# lp_propeller.net
KiCad netlist of a schematic drawn in EAGLE
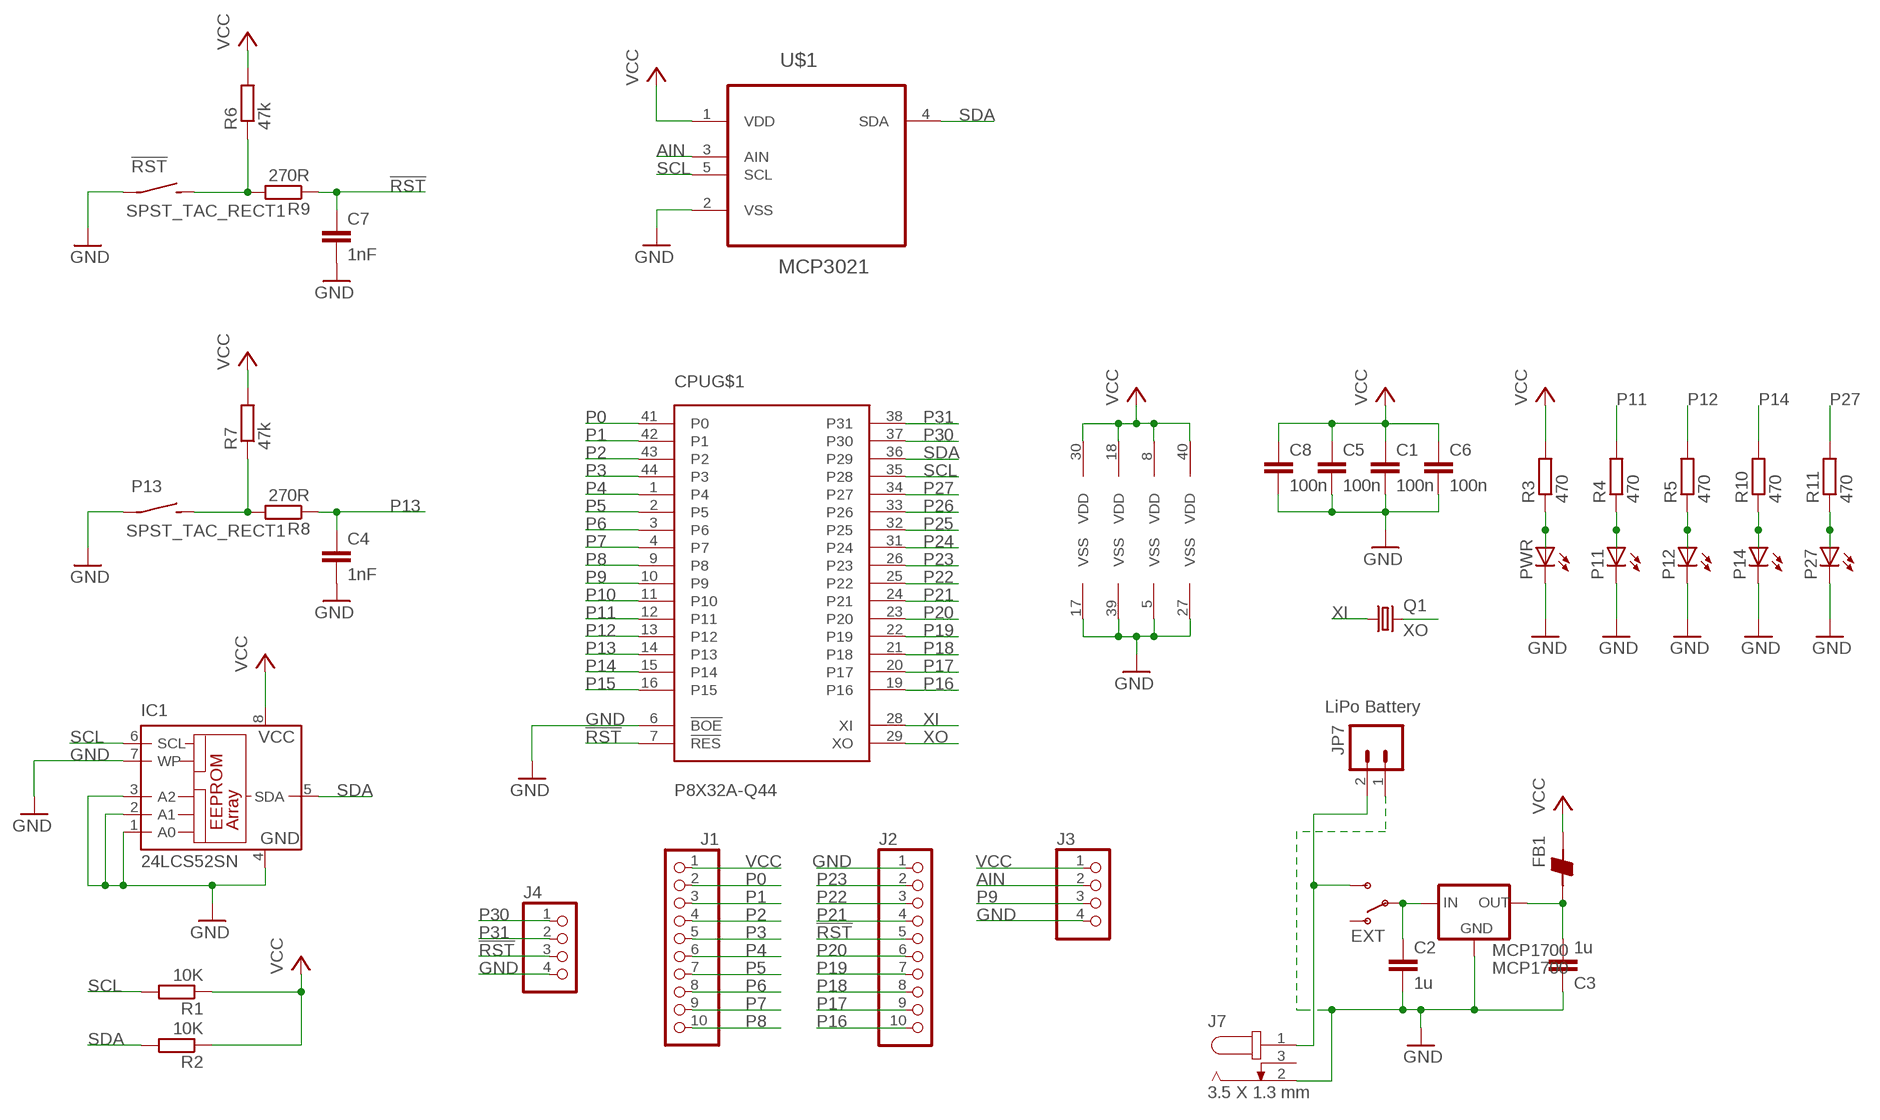
[diagram p0: schematic, sheet 1]

(export (version "E")
  (design (tool "Eeschema 10.0.6"))
  (components
    (comp (ref "!RST")
      (value "SPST_TAC_RECT1")
      (footprint "eagle-import:6MMTACTILE_RECT")
      (libsource (lib "eagle-import") (part "SPST_TAC_RECT1"))
    )
    (comp (ref "C1")
      (value "100n")
      (footprint "eagle-import:C0805")
      (libsource (lib "eagle-import") (part "C-EUC0805"))
    )
    (comp (ref "C2")
      (value "1u")
      (footprint "eagle-import:C0805")
      (libsource (lib "eagle-import") (part "C-EUC0805"))
    )
    (comp (ref "C3")
      (value "1u")
      (footprint "eagle-import:C0805")
      (libsource (lib "eagle-import") (part "C-EUC0805"))
    )
    (comp (ref "C4")
      (value "1nF")
      (footprint "eagle-import:C0805")
      (libsource (lib "eagle-import") (part "resistor_C-EUC0805"))
    )
    (comp (ref "C5")
      (value "100n")
      (footprint "eagle-import:C0805")
      (libsource (lib "eagle-import") (part "C-EUC0805"))
    )
    (comp (ref "C6")
      (value "100n")
      (footprint "eagle-import:C0805")
      (libsource (lib "eagle-import") (part "C-EUC0805"))
    )
    (comp (ref "C7")
      (value "1nF")
      (footprint "eagle-import:C0805")
      (libsource (lib "eagle-import") (part "resistor_C-EUC0805"))
    )
    (comp (ref "C8")
      (value "100n")
      (footprint "eagle-import:C0805")
      (libsource (lib "eagle-import") (part "C-EUC0805"))
    )
    (comp (ref "CPU")
      (value "P8X32A-Q44")
      (footprint "eagle-import:LQFP-44")
      (libsource (lib "eagle-import") (part "P8X32A-Q44"))
    )
    (comp (ref "FB1")
      (value "BEAD-0805")
      (footprint "eagle-import:0805")
      (libsource (lib "eagle-import") (part "BEAD-0805"))
    )
    (comp (ref "IC1")
      (value "24LCS52SN")
      (footprint "eagle-import:SO-08")
      (fields (field (name "MF") "MICROCHIP") (field (name "MPN") "24LCS52-I/SN"))
      (libsource (lib "eagle-import") (part "24SNLCS52"))
    )
    (comp (ref "J1")
      (value "PH1X10OCT076")
      (footprint "eagle-import:PH1X10OCT76")
      (libsource (lib "eagle-import") (part "PH1X10OCT076"))
    )
    (comp (ref "J2")
      (value "PH1X10OCT076")
      (footprint "eagle-import:PH1X10OCT76")
      (libsource (lib "eagle-import") (part "PH1X10OCT076"))
    )
    (comp (ref "J3")
      (value "PINHD-1X4")
      (footprint "eagle-import:1X04")
      (libsource (lib "eagle-import") (part "PINHD-1X4"))
    )
    (comp (ref "J4")
      (value "PINHD-1X4")
      (footprint "eagle-import:1X04")
      (libsource (lib "eagle-import") (part "PINHD-1X4"))
    )
    (comp (ref "J7")
      (value "3.5 X 1.3 mm")
      (footprint "eagle-import:3.5X1.3MM_DC_JACK")
      (libsource (lib "eagle-import") (part "DC_JACK_3.5X1.3MM"))
    )
    (comp (ref "JP7")
      (value "LiPo Battery")
      (footprint "eagle-import:JST-2-PTH")
      (libsource (lib "eagle-import") (part "M02JST-PTH-2"))
    )
    (comp (ref "MCP1700")
      (value "MCP1700")
      (footprint "eagle-import:SOT-23")
      (libsource (lib "eagle-import") (part "MCP1700SOT-23"))
    )
    (comp (ref "ON")
      (value "EXT")
      (footprint "eagle-import:SWITCH-SPDT")
      (libsource (lib "eagle-import") (part "SWITCH-SPSTPTH"))
    )
    (comp (ref "P11")
      (value "LEDCHIPLED_1206")
      (footprint "eagle-import:CHIPLED_1206")
      (libsource (lib "eagle-import") (part "LEDCHIPLED_1206"))
    )
    (comp (ref "P12")
      (value "LEDCHIPLED_1206")
      (footprint "eagle-import:CHIPLED_1206")
      (libsource (lib "eagle-import") (part "LEDCHIPLED_1206"))
    )
    (comp (ref "P13")
      (value "SPST_TAC_RECT1")
      (footprint "eagle-import:6MMTACTILE_RECT")
      (libsource (lib "eagle-import") (part "SPST_TAC_RECT1"))
    )
    (comp (ref "P14")
      (value "LEDCHIPLED_1206")
      (footprint "eagle-import:CHIPLED_1206")
      (libsource (lib "eagle-import") (part "LEDCHIPLED_1206"))
    )
    (comp (ref "P27")
      (value "LEDCHIPLED_1206")
      (footprint "eagle-import:CHIPLED_1206")
      (libsource (lib "eagle-import") (part "LEDCHIPLED_1206"))
    )
    (comp (ref "PWR")
      (value "LEDCHIPLED_1206")
      (footprint "eagle-import:CHIPLED_1206")
      (libsource (lib "eagle-import") (part "LEDCHIPLED_1206"))
    )
    (comp (ref "Q1")
      (value "CRYSTALHC49S")
      (footprint "eagle-import:HC49_S")
      (libsource (lib "eagle-import") (part "CRYSTALHC49S"))
    )
    (comp (ref "R1")
      (value "10K")
      (footprint "eagle-import:R0805")
      (libsource (lib "eagle-import") (part "R-EU_R0805"))
    )
    (comp (ref "R2")
      (value "10K")
      (footprint "eagle-import:R0805")
      (libsource (lib "eagle-import") (part "R-EU_R0805"))
    )
    (comp (ref "R3")
      (value "470")
      (footprint "eagle-import:R0805")
      (libsource (lib "eagle-import") (part "R-EU_R0805"))
    )
    (comp (ref "R4")
      (value "470")
      (footprint "eagle-import:R0805")
      (libsource (lib "eagle-import") (part "R-EU_R0805"))
    )
    (comp (ref "R5")
      (value "470")
      (footprint "eagle-import:R0805")
      (libsource (lib "eagle-import") (part "R-EU_R0805"))
    )
    (comp (ref "R6")
      (value "47k")
      (footprint "eagle-import:R0805")
      (libsource (lib "eagle-import") (part "R-EU_R0805"))
    )
    (comp (ref "R7")
      (value "47k")
      (footprint "eagle-import:R0805")
      (libsource (lib "eagle-import") (part "R-EU_R0805"))
    )
    (comp (ref "R8")
      (value "270R")
      (footprint "eagle-import:R0805")
      (libsource (lib "eagle-import") (part "R-EU_R0805"))
    )
    (comp (ref "R9")
      (value "270R")
      (footprint "eagle-import:R0805")
      (libsource (lib "eagle-import") (part "R-EU_R0805"))
    )
    (comp (ref "R10")
      (value "470")
      (footprint "eagle-import:R0805")
      (libsource (lib "eagle-import") (part "R-EU_R0805"))
    )
    (comp (ref "R11")
      (value "470")
      (footprint "eagle-import:R0805")
      (libsource (lib "eagle-import") (part "R-EU_R0805"))
    )
    (comp (ref "U$1")
      (value "MCP3021")
      (footprint "eagle-import:SOT95P270X145-5N")
      (fields (field (name "MPN") "MCP3021A5T-E/OT"))
      (libsource (lib "eagle-import") (part "MCP3021A5T-E/OT"))
    )
  )
  (nets
    (net (code "1") (name "/AIN") (class "Default")
      (node (ref "J3") (pin "2") (pinfunction "2_2") (pintype "passive"))
      (node (ref "U$1") (pin "3") (pinfunction "AIN_3") (pintype "input"))
    )
    (net (code "2") (name "/P0") (class "Default")
      (node (ref "CPU") (pin "41") (pinfunction "P0_41") (pintype "bidirectional"))
      (node (ref "J1") (pin "2") (pinfunction "2_2") (pintype "passive"))
    )
    (net (code "3") (name "/P1") (class "Default")
      (node (ref "CPU") (pin "42") (pinfunction "P1_42") (pintype "bidirectional"))
      (node (ref "J1") (pin "3") (pinfunction "3_3") (pintype "passive"))
    )
    (net (code "4") (name "/P2") (class "Default")
      (node (ref "CPU") (pin "43") (pinfunction "P2_43") (pintype "bidirectional"))
      (node (ref "J1") (pin "4") (pinfunction "4_4") (pintype "passive"))
    )
    (net (code "5") (name "/P3") (class "Default")
      (node (ref "CPU") (pin "44") (pinfunction "P3_44") (pintype "bidirectional"))
      (node (ref "J1") (pin "5") (pinfunction "5_5") (pintype "passive"))
    )
    (net (code "6") (name "/P4") (class "Default")
      (node (ref "CPU") (pin "1") (pinfunction "P4_1") (pintype "bidirectional"))
      (node (ref "J1") (pin "6") (pinfunction "6_6") (pintype "passive"))
    )
    (net (code "7") (name "/P5") (class "Default")
      (node (ref "CPU") (pin "2") (pinfunction "P5_2") (pintype "bidirectional"))
      (node (ref "J1") (pin "7") (pinfunction "7_7") (pintype "passive"))
    )
    (net (code "8") (name "/P6") (class "Default")
      (node (ref "CPU") (pin "3") (pinfunction "P6_3") (pintype "bidirectional"))
      (node (ref "J1") (pin "8") (pinfunction "8_8") (pintype "passive"))
    )
    (net (code "9") (name "/P7") (class "Default")
      (node (ref "CPU") (pin "4") (pinfunction "P7_4") (pintype "bidirectional"))
      (node (ref "J1") (pin "9") (pinfunction "9_9") (pintype "passive"))
    )
    (net (code "10") (name "/P8") (class "Default")
      (node (ref "CPU") (pin "9") (pinfunction "P8_9") (pintype "bidirectional"))
      (node (ref "J1") (pin "10") (pinfunction "10_10") (pintype "passive"))
    )
    (net (code "11") (name "/P9") (class "Default")
      (node (ref "CPU") (pin "10") (pinfunction "P9_10") (pintype "bidirectional"))
      (node (ref "J3") (pin "3") (pinfunction "3_3") (pintype "passive"))
    )
    (net (code "12") (name "/P10") (class "Default")
      (node (ref "CPU") (pin "11") (pinfunction "P10_11") (pintype "bidirectional"))
    )
    (net (code "13") (name "/P11") (class "Default")
      (node (ref "CPU") (pin "12") (pinfunction "P11_12") (pintype "bidirectional"))
      (node (ref "R4") (pin "2") (pinfunction "2_2") (pintype "passive"))
    )
    (net (code "14") (name "/P12") (class "Default")
      (node (ref "CPU") (pin "13") (pinfunction "P12_13") (pintype "bidirectional"))
      (node (ref "R5") (pin "2") (pinfunction "2_2") (pintype "passive"))
    )
    (net (code "15") (name "/P13") (class "Default")
      (node (ref "C4") (pin "1") (pinfunction "1_1") (pintype "passive"))
      (node (ref "CPU") (pin "14") (pinfunction "P13_14") (pintype "bidirectional"))
      (node (ref "R8") (pin "1") (pinfunction "1_1") (pintype "passive"))
    )
    (net (code "16") (name "/P14") (class "Default")
      (node (ref "CPU") (pin "15") (pinfunction "P14_15") (pintype "bidirectional"))
      (node (ref "R10") (pin "2") (pinfunction "2_2") (pintype "passive"))
    )
    (net (code "17") (name "/P15") (class "Default")
      (node (ref "CPU") (pin "16") (pinfunction "P15_16") (pintype "bidirectional"))
    )
    (net (code "18") (name "/P16") (class "Default")
      (node (ref "CPU") (pin "19") (pinfunction "P16_19") (pintype "bidirectional"))
      (node (ref "J2") (pin "10") (pinfunction "10_10") (pintype "passive"))
    )
    (net (code "19") (name "/P17") (class "Default")
      (node (ref "CPU") (pin "20") (pinfunction "P17_20") (pintype "bidirectional"))
      (node (ref "J2") (pin "9") (pinfunction "9_9") (pintype "passive"))
    )
    (net (code "20") (name "/P18") (class "Default")
      (node (ref "CPU") (pin "21") (pinfunction "P18_21") (pintype "bidirectional"))
      (node (ref "J2") (pin "8") (pinfunction "8_8") (pintype "passive"))
    )
    (net (code "21") (name "/P19") (class "Default")
      (node (ref "CPU") (pin "22") (pinfunction "P19_22") (pintype "bidirectional"))
      (node (ref "J2") (pin "7") (pinfunction "7_7") (pintype "passive"))
    )
    (net (code "22") (name "/P20") (class "Default")
      (node (ref "CPU") (pin "23") (pinfunction "P20_23") (pintype "bidirectional"))
      (node (ref "J2") (pin "6") (pinfunction "6_6") (pintype "passive"))
    )
    (net (code "23") (name "/P21") (class "Default")
      (node (ref "CPU") (pin "24") (pinfunction "P21_24") (pintype "bidirectional"))
      (node (ref "J2") (pin "4") (pinfunction "4_4") (pintype "passive"))
    )
    (net (code "24") (name "/P22") (class "Default")
      (node (ref "CPU") (pin "25") (pinfunction "P22_25") (pintype "bidirectional"))
      (node (ref "J2") (pin "3") (pinfunction "3_3") (pintype "passive"))
    )
    (net (code "25") (name "/P23") (class "Default")
      (node (ref "CPU") (pin "26") (pinfunction "P23_26") (pintype "bidirectional"))
      (node (ref "J2") (pin "2") (pinfunction "2_2") (pintype "passive"))
    )
    (net (code "26") (name "/P24") (class "Default")
      (node (ref "CPU") (pin "31") (pinfunction "P24_31") (pintype "bidirectional"))
    )
    (net (code "27") (name "/P25") (class "Default")
      (node (ref "CPU") (pin "32") (pinfunction "P25_32") (pintype "bidirectional"))
    )
    (net (code "28") (name "/P26") (class "Default")
      (node (ref "CPU") (pin "33") (pinfunction "P26_33") (pintype "bidirectional"))
    )
    (net (code "29") (name "/P27") (class "Default")
      (node (ref "CPU") (pin "34") (pinfunction "P27_34") (pintype "bidirectional"))
      (node (ref "R11") (pin "2") (pinfunction "2_2") (pintype "passive"))
    )
    (net (code "30") (name "/P30") (class "Default")
      (node (ref "CPU") (pin "37") (pinfunction "P30_37") (pintype "bidirectional"))
      (node (ref "J4") (pin "1") (pinfunction "1_1") (pintype "passive"))
    )
    (net (code "31") (name "/P31") (class "Default")
      (node (ref "CPU") (pin "38") (pinfunction "P31_38") (pintype "bidirectional"))
      (node (ref "J4") (pin "2") (pinfunction "2_2") (pintype "passive"))
    )
    (net (code "32") (name "/SCL") (class "Default")
      (node (ref "CPU") (pin "35") (pinfunction "P28_35") (pintype "bidirectional"))
      (node (ref "IC1") (pin "6") (pinfunction "SCL_6") (pintype "input"))
      (node (ref "R1") (pin "2") (pinfunction "2_2") (pintype "passive"))
      (node (ref "U$1") (pin "5") (pinfunction "SCL_5") (pintype "input"))
    )
    (net (code "33") (name "/SDA") (class "Default")
      (node (ref "CPU") (pin "36") (pinfunction "P29_36") (pintype "bidirectional"))
      (node (ref "IC1") (pin "5") (pinfunction "SDA_5") (pintype "bidirectional"))
      (node (ref "R2") (pin "2") (pinfunction "2_2") (pintype "passive"))
      (node (ref "U$1") (pin "4") (pinfunction "SDA_4") (pintype "bidirectional"))
    )
    (net (code "34") (name "/XI") (class "Default")
      (node (ref "CPU") (pin "28") (pinfunction "XI_28") (pintype "input"))
      (node (ref "Q1") (pin "1") (pinfunction "1_1") (pintype "passive"))
    )
    (net (code "35") (name "/XO") (class "Default")
      (node (ref "CPU") (pin "29") (pinfunction "XO_29") (pintype "output"))
      (node (ref "Q1") (pin "2") (pinfunction "2_2") (pintype "passive"))
    )
    (net (code "36") (name "/~{RST}") (class "Default")
      (node (ref "C7") (pin "1") (pinfunction "1_1") (pintype "passive"))
      (node (ref "CPU") (pin "7") (pinfunction "~{RES}_7") (pintype "bidirectional"))
      (node (ref "J2") (pin "5") (pinfunction "5_5") (pintype "passive"))
      (node (ref "J4") (pin "3") (pinfunction "3_3") (pintype "passive"))
      (node (ref "R9") (pin "1") (pinfunction "1_1") (pintype "passive"))
    )
    (net (code "37") (name "GND") (class "Default")
      (node (ref "!RST") (pin "P$1") (pinfunction "P_P$1") (pintype "passive"))
      (node (ref "C1") (pin "2") (pinfunction "2_2") (pintype "passive"))
      (node (ref "C2") (pin "2") (pinfunction "2_2") (pintype "passive"))
      (node (ref "C3") (pin "1") (pinfunction "1_1") (pintype "passive"))
      (node (ref "C4") (pin "2") (pinfunction "2_2") (pintype "passive"))
      (node (ref "C5") (pin "2") (pinfunction "2_2") (pintype "passive"))
      (node (ref "C6") (pin "2") (pinfunction "2_2") (pintype "passive"))
      (node (ref "C7") (pin "2") (pinfunction "2_2") (pintype "passive"))
      (node (ref "C8") (pin "2") (pinfunction "2_2") (pintype "passive"))
      (node (ref "CPU") (pin "17") (pinfunction "VSS_17") (pintype "input"))
      (node (ref "CPU") (pin "27") (pinfunction "VSS_27") (pintype "input"))
      (node (ref "CPU") (pin "39") (pinfunction "VSS_39") (pintype "input"))
      (node (ref "CPU") (pin "5") (pinfunction "VSS_5") (pintype "input"))
      (node (ref "CPU") (pin "6") (pinfunction "~{BOE}_6") (pintype "input"))
      (node (ref "IC1") (pin "1") (pinfunction "A0_1") (pintype "input"))
      (node (ref "IC1") (pin "2") (pinfunction "A1_2") (pintype "input"))
      (node (ref "IC1") (pin "3") (pinfunction "A2_3") (pintype "input"))
      (node (ref "IC1") (pin "4") (pinfunction "GND_4") (pintype "power_in"))
      (node (ref "IC1") (pin "7") (pinfunction "WP_7") (pintype "input"))
      (node (ref "J2") (pin "1") (pinfunction "1_1") (pintype "passive"))
      (node (ref "J3") (pin "4") (pinfunction "4_4") (pintype "passive"))
      (node (ref "J4") (pin "4") (pinfunction "4_4") (pintype "passive"))
      (node (ref "J7") (pin "2") (pinfunction "2_2") (pintype "passive"))
      (node (ref "JP7") (pin "1") (pinfunction "1_1") (pintype "passive"))
      (node (ref "MCP1700") (pin "1") (pinfunction "GND_1") (pintype "input"))
      (node (ref "P11") (pin "C") (pinfunction "C_C") (pintype "passive"))
      (node (ref "P12") (pin "C") (pinfunction "C_C") (pintype "passive"))
      (node (ref "P13") (pin "P$1") (pinfunction "P_P$1") (pintype "passive"))
      (node (ref "P14") (pin "C") (pinfunction "C_C") (pintype "passive"))
      (node (ref "P27") (pin "C") (pinfunction "C_C") (pintype "passive"))
      (node (ref "PWR") (pin "C") (pinfunction "C_C") (pintype "passive"))
      (node (ref "U$1") (pin "2") (pinfunction "VSS_2") (pintype "passive"))
    )
    (net (code "38") (name "Net-(!RST-S)") (class "Default")
      (node (ref "!RST") (pin "P$2") (pinfunction "S_P$2") (pintype "passive"))
      (node (ref "R6") (pin "1") (pinfunction "1_1") (pintype "passive"))
      (node (ref "R9") (pin "2") (pinfunction "2_2") (pintype "passive"))
    )
    (net (code "39") (name "Net-(FB1-P$1)") (class "Default")
      (node (ref "C3") (pin "2") (pinfunction "2_2") (pintype "passive"))
      (node (ref "FB1") (pin "1") (pinfunction "P$1_1") (pintype "passive"))
      (node (ref "MCP1700") (pin "2") (pinfunction "OUT_2") (pintype "passive"))
    )
    (net (code "40") (name "Net-(MCP1700-IN)") (class "Default")
      (node (ref "C2") (pin "1") (pinfunction "1_1") (pintype "passive"))
      (node (ref "MCP1700") (pin "3") (pinfunction "IN_3") (pintype "input"))
      (node (ref "ON") (pin "2") (pinfunction "P_2") (pintype "passive"))
    )
    (net (code "41") (name "Net-(ON-S)") (class "Default")
      (node (ref "J7") (pin "1") (pinfunction "1_1") (pintype "passive"))
      (node (ref "JP7") (pin "2") (pinfunction "2_2") (pintype "passive"))
      (node (ref "ON") (pin "3") (pinfunction "S_3") (pintype "passive"))
    )
    (net (code "42") (name "Net-(P11-PadA)") (class "Default")
      (node (ref "P11") (pin "A") (pinfunction "A_A") (pintype "passive"))
      (node (ref "R4") (pin "1") (pinfunction "1_1") (pintype "passive"))
    )
    (net (code "43") (name "Net-(P12-PadA)") (class "Default")
      (node (ref "P12") (pin "A") (pinfunction "A_A") (pintype "passive"))
      (node (ref "R5") (pin "1") (pinfunction "1_1") (pintype "passive"))
    )
    (net (code "44") (name "Net-(P13-S)") (class "Default")
      (node (ref "P13") (pin "P$2") (pinfunction "S_P$2") (pintype "passive"))
      (node (ref "R7") (pin "1") (pinfunction "1_1") (pintype "passive"))
      (node (ref "R8") (pin "2") (pinfunction "2_2") (pintype "passive"))
    )
    (net (code "45") (name "Net-(P14-PadA)") (class "Default")
      (node (ref "P14") (pin "A") (pinfunction "A_A") (pintype "passive"))
      (node (ref "R10") (pin "1") (pinfunction "1_1") (pintype "passive"))
    )
    (net (code "46") (name "Net-(P27-PadA)") (class "Default")
      (node (ref "P27") (pin "A") (pinfunction "A_A") (pintype "passive"))
      (node (ref "R11") (pin "1") (pinfunction "1_1") (pintype "passive"))
    )
    (net (code "47") (name "Net-(PWR-PadA)") (class "Default")
      (node (ref "PWR") (pin "A") (pinfunction "A_A") (pintype "passive"))
      (node (ref "R3") (pin "1") (pinfunction "1_1") (pintype "passive"))
    )
    (net (code "48") (name "VCC") (class "Default")
      (node (ref "C1") (pin "1") (pinfunction "1_1") (pintype "passive"))
      (node (ref "C5") (pin "1") (pinfunction "1_1") (pintype "passive"))
      (node (ref "C6") (pin "1") (pinfunction "1_1") (pintype "passive"))
      (node (ref "C8") (pin "1") (pinfunction "1_1") (pintype "passive"))
      (node (ref "CPU") (pin "18") (pinfunction "VDD_18") (pintype "input"))
      (node (ref "CPU") (pin "30") (pinfunction "VDD_30") (pintype "input"))
      (node (ref "CPU") (pin "40") (pinfunction "VDD_40") (pintype "input"))
      (node (ref "CPU") (pin "8") (pinfunction "VDD_8") (pintype "input"))
      (node (ref "FB1") (pin "2") (pinfunction "P$2_2") (pintype "passive"))
      (node (ref "IC1") (pin "8") (pinfunction "VCC_8") (pintype "power_in"))
      (node (ref "J1") (pin "1") (pinfunction "1_1") (pintype "passive"))
      (node (ref "J3") (pin "1") (pinfunction "1_1") (pintype "passive"))
      (node (ref "R1") (pin "1") (pinfunction "1_1") (pintype "passive"))
      (node (ref "R2") (pin "1") (pinfunction "1_1") (pintype "passive"))
      (node (ref "R3") (pin "2") (pinfunction "2_2") (pintype "passive"))
      (node (ref "R6") (pin "2") (pinfunction "2_2") (pintype "passive"))
      (node (ref "R7") (pin "2") (pinfunction "2_2") (pintype "passive"))
      (node (ref "U$1") (pin "1") (pinfunction "VDD_1") (pintype "power_in"))
    )
    (net (code "49") (name "unconnected-(J7-Pad3)") (class "Default")
      (node (ref "J7") (pin "3") (pinfunction "3_3") (pintype "passive"))
    )
    (net (code "50") (name "unconnected-(ON-O-Pad1)") (class "Default")
      (node (ref "ON") (pin "1") (pinfunction "O_1") (pintype "passive"))
    )
  )
)
